# ProPrj_LoRA_Transmitter_Atmega328u_2025-.net
KiCad netlist of a schematic drawn in EasyEDA Pro
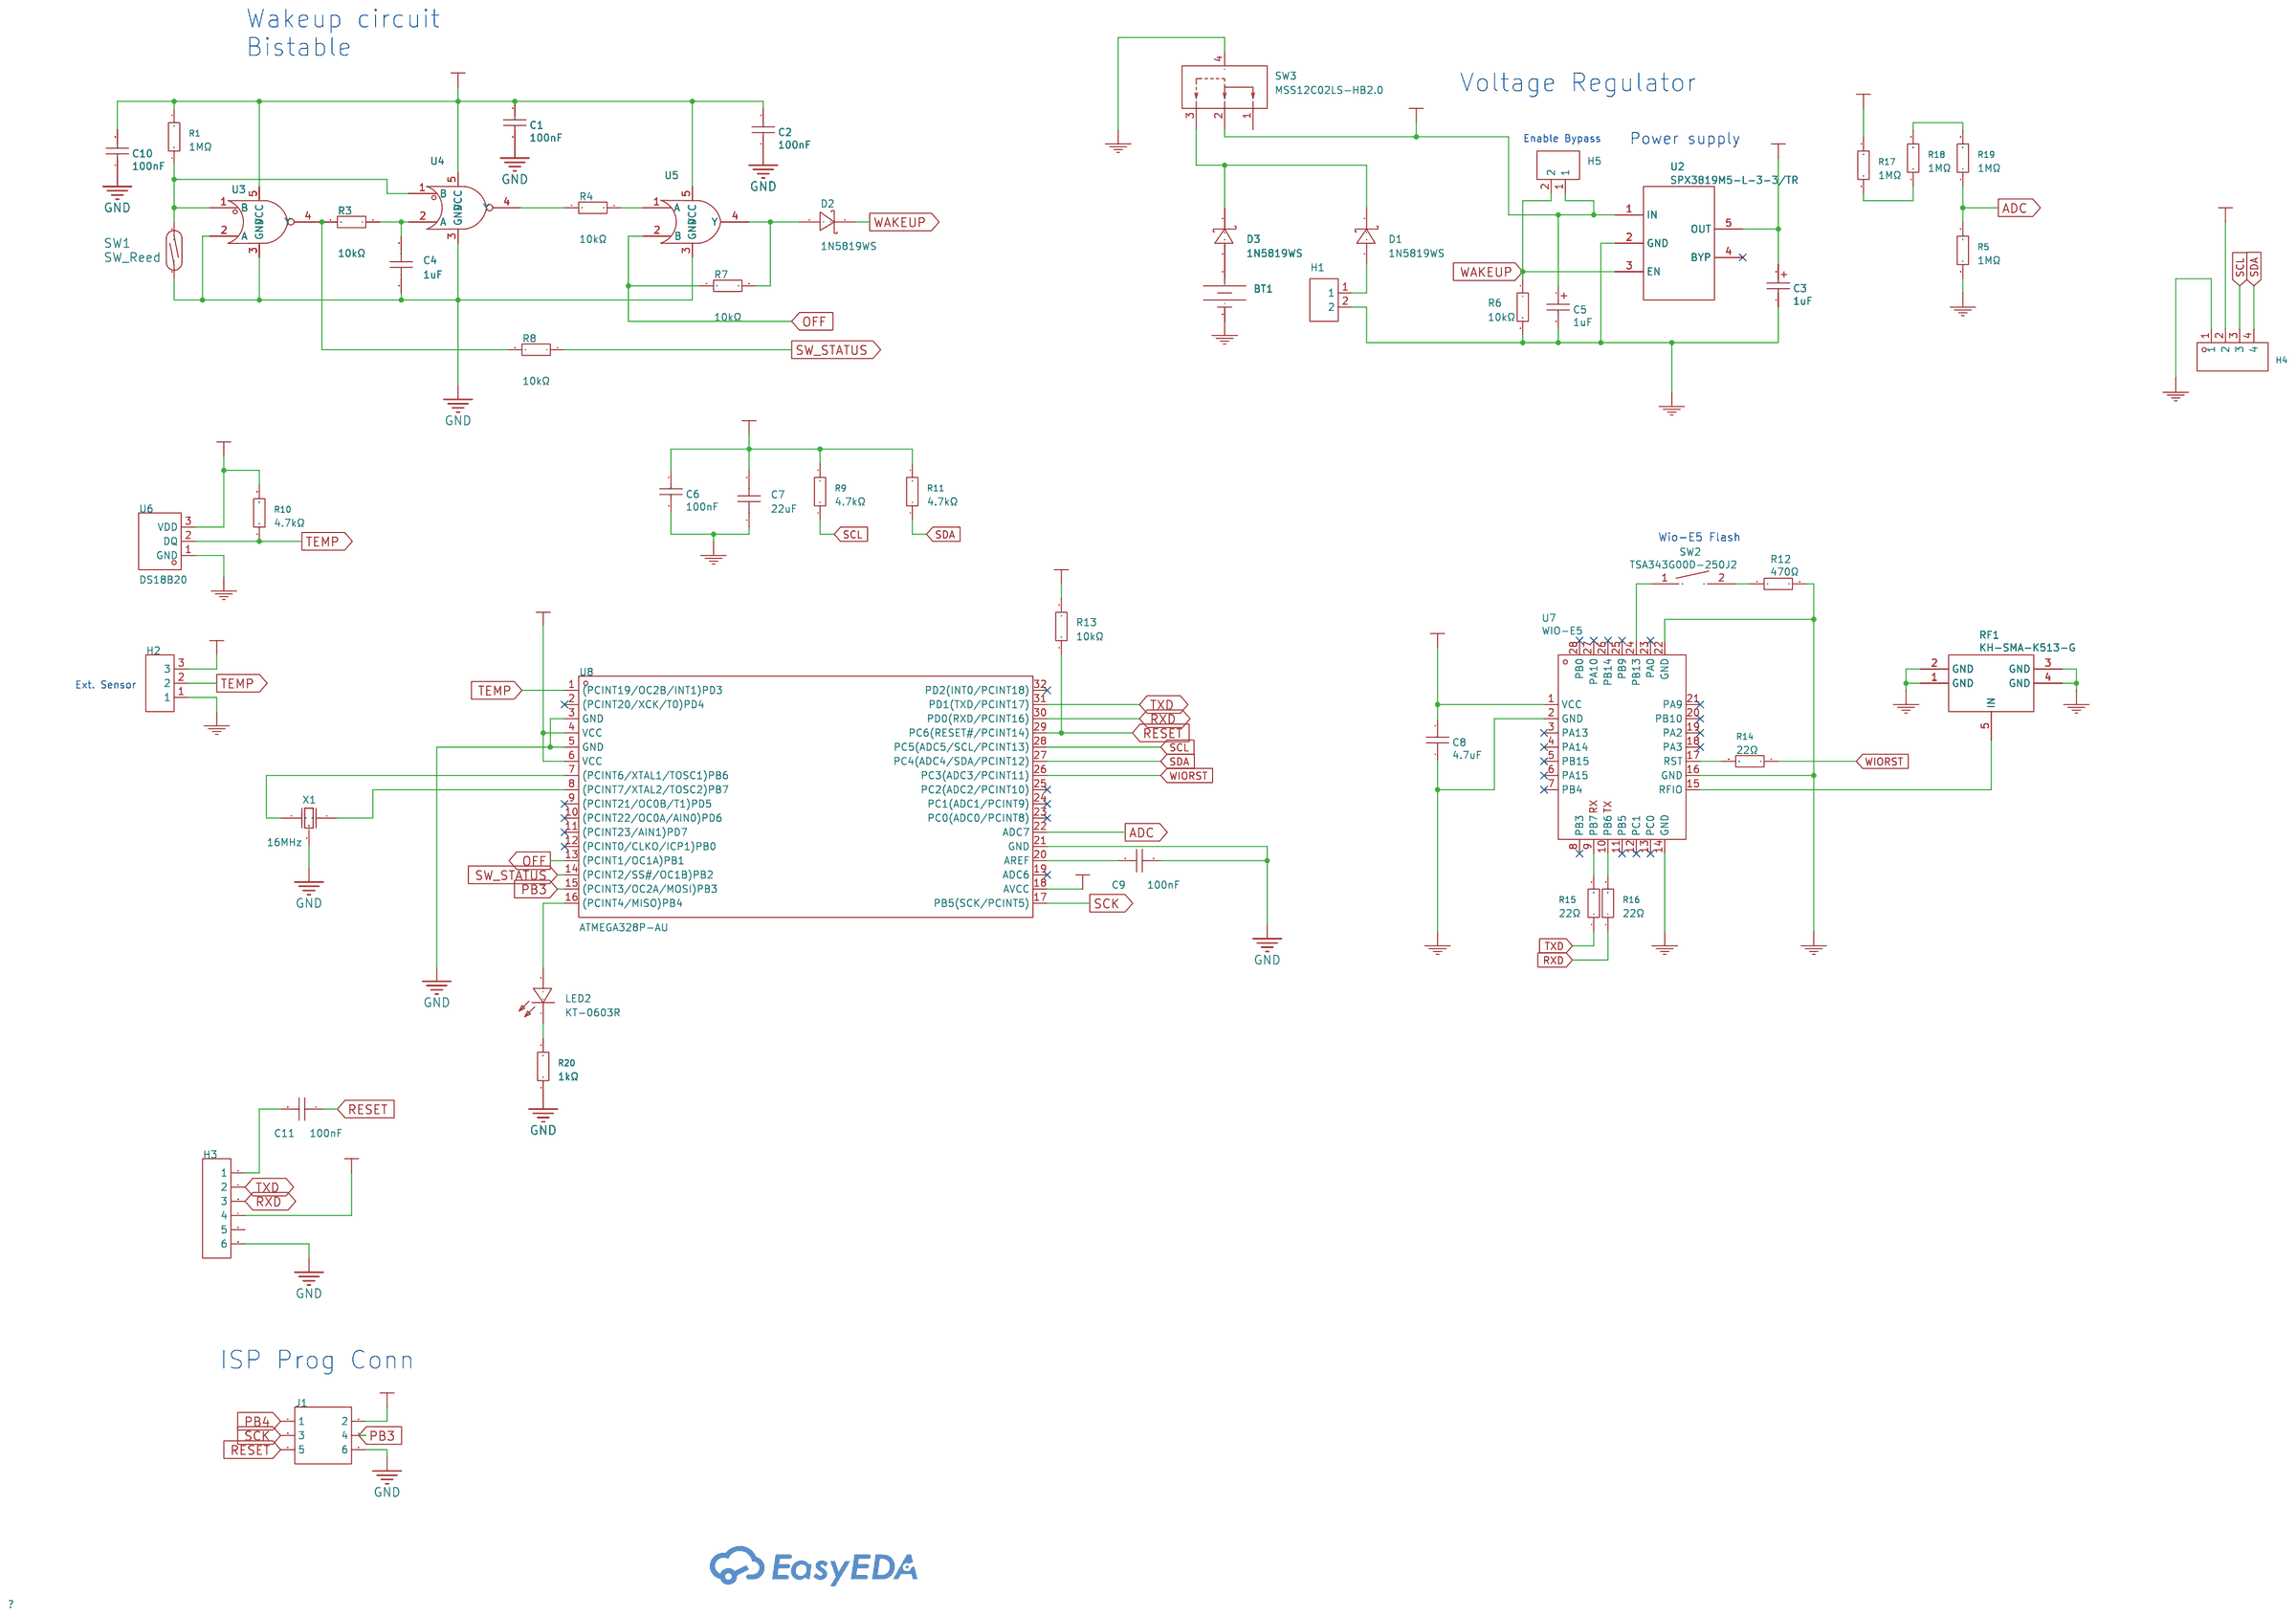
[diagram p0: schematic sheet]

(export (version "E")
  (design (tool "Eeschema 10.0.6"))
  (components
    (comp (ref "BT1")
      (value "BH-18650-4")
      (footprint "easyedapro:BAT-SMD_BH-18650-4")
      (fields (field (name "Manufacturer") "HanElectricity(瀚源)"))
      (libsource (lib "easyedapro") (part "BH-18650-4"))
    )
    (comp (ref "C1") (value "100nF") (libsource (lib "easyedapro") (part "100nF")))
    (comp (ref "C2") (value "100nF") (libsource (lib "easyedapro") (part "100nF")))
    (comp (ref "C3")
      (value "1uF")
      (footprint "easyedapro:footprint_777a")
      (fields (field (name "Manufacturer Part") "TAJA105K035RNJ") (field (name "Manufacturer") "Kyocera AVX"))
      (libsource (lib "easyedapro") (part "1uF"))
    )
    (comp (ref "C4")
      (value "1uF")
      (footprint "easyedapro:C0402")
      (description "Capacitance:1uF Tolerance:±10% Tolerance:±10% Voltage Rating:25V Temperature Coefficient:X5R")
      (fields
        (field (name "Manufacturer Part") "CL05A105KA5NQNC")
        (field (name "Manufacturer") "SAMSUNG(三星)")
      )
      (libsource (lib "easyedapro") (part "CL05A105KA5NQNC"))
    )
    (comp (ref "C5")
      (value "1uF")
      (footprint "easyedapro:footprint_777a")
      (fields (field (name "Manufacturer Part") "TAJA105K035RNJ") (field (name "Manufacturer") "Kyocera AVX"))
      (libsource (lib "easyedapro") (part "1uF"))
    )
    (comp (ref "C6") (value "100nF") (libsource (lib "easyedapro") (part "100nF")))
    (comp (ref "C7")
      (value "22uF")
      (footprint "easyedapro:C0603")
      (fields
        (field (name "Manufacturer Part") "CL10A226MQ8NRNC")
        (field (name "Manufacturer") "SAMSUNG(三星)")
      )
      (libsource (lib "easyedapro") (part "CL10A226MQ8NRNC"))
    )
    (comp (ref "C8")
      (value "4.7uF")
      (footprint "easyedapro:footprint_3af0")
      (fields
        (field (name "Manufacturer Part") "CL10A475KO8NNNC")
        (field (name "Manufacturer") "SAMSUNG(三星)")
      )
      (libsource (lib "easyedapro") (part "4.7uF"))
    )
    (comp (ref "C9") (value "100nF") (libsource (lib "easyedapro") (part "100nF")))
    (comp (ref "C10") (value "100nF") (libsource (lib "easyedapro") (part "100nF")))
    (comp (ref "C11") (value "100nF") (libsource (lib "easyedapro") (part "100nF")))
    (comp (ref "D1")
      (value "1N5819WS")
      (footprint "easyedapro:SOD-323_L1.8-W1.3-LS2.5-RD")
      (description "Forward Voltage (Vf@If):600mV@1A Reverse Voltage (Vr):40V Rectified Current:1A")
      (fields (field (name "Manufacturer") "Hottech(合科泰)"))
      (libsource (lib "easyedapro") (part "1N5819WS"))
    )
    (comp (ref "D2")
      (value "1N5819WS")
      (footprint "easyedapro:SOD-323_L1.8-W1.3-LS2.5-RD")
      (description "Forward Voltage (Vf@If):600mV@1A Reverse Voltage (Vr):40V Rectified Current:1A")
      (fields (field (name "Manufacturer") "Hottech(合科泰)"))
      (libsource (lib "easyedapro") (part "1N5819WS"))
    )
    (comp (ref "D3")
      (value "1N5819WS")
      (footprint "easyedapro:SOD-323_L1.8-W1.3-LS2.5-RD")
      (description "Forward Voltage (Vf@If):600mV@1A Reverse Voltage (Vr):40V Rectified Current:1A")
      (fields (field (name "Manufacturer") "Hottech(合科泰)"))
      (libsource (lib "easyedapro") (part "1N5819WS"))
    )
    (comp (ref "H1")
      (value "PZ254V-11-02P")
      (footprint "easyedapro:HDR-TH_2P-P2.54-V-M")
      (fields (field (name "Manufacturer") "XFCN(兴飞)"))
      (libsource (lib "easyedapro") (part "PZ254V-11-02P"))
    )
    (comp (ref "H2")
      (value "PZ254V-11-03P")
      (footprint "easyedapro:HDR-TH_3P-P2.54-V-M")
      (fields (field (name "Manufacturer") "XFCN(兴飞)"))
      (libsource (lib "easyedapro") (part "PZ254V-11-03P_C2937625"))
    )
    (comp (ref "H3")
      (value "2.54-1x6P直针")
      (footprint "easyedapro:HDR-TH_6P-P2.54-V-M-1")
      (fields (field (name "Manufacturer") "BOOMELE(博穆精密)"))
      (libsource (lib "easyedapro") (part "Header-Male-2.54_1x6"))
    )
    (comp (ref "H4")
      (value "PZ254V-11-04P")
      (footprint "easyedapro:HDR-TH_4P-P2.54-V-M")
      (fields (field (name "Manufacturer") "XFCN(兴飞)"))
      (libsource (lib "easyedapro") (part "PZ254V-11-04P_C2691448"))
    )
    (comp (ref "H5")
      (value "PZ254V-11-02P")
      (footprint "easyedapro:HDR-TH_2P-P2.54-V-M")
      (fields (field (name "Manufacturer") "XFCN(兴飞)"))
      (libsource (lib "easyedapro") (part "PZ254V-11-02P"))
    )
    (comp (ref "J1")
      (value "2.54-2*3P针")
      (footprint "easyedapro:HDR-TH_6P-P2.54-V-M-R2-C3-S2.54-1")
      (fields (field (name "Manufacturer") "BOOMELE(博穆精密)"))
      (libsource (lib "easyedapro") (part "Header-Male-2.54_2x3"))
    )
    (comp (ref "LED2")
      (value "KT-0603R")
      (footprint "easyedapro:LED0603-RD")
      (fields (field (name "Manufacturer") "KENTO"))
      (libsource (lib "easyedapro") (part "KT-0603R"))
    )
    (comp (ref "R1")
      (value "1MΩ")
      (footprint "easyedapro:R0402")
      (fields
        (field (name "Manufacturer Part") "0402WGF1004TCE")
        (field (name "Manufacturer") "UNI-ROYAL(厚声)")
      )
      (libsource (lib "easyedapro") (part "0402WGF1004TCE"))
    )
    (comp (ref "R3")
      (value "10kΩ")
      (footprint "easyedapro:R0402")
      (fields
        (field (name "Manufacturer Part") "0402WGF1002TCE")
        (field (name "Manufacturer") "UNI-ROYAL(厚声)")
      )
      (libsource (lib "easyedapro") (part "0402WGF1002TCE"))
    )
    (comp (ref "R4")
      (value "10kΩ")
      (footprint "easyedapro:R0402")
      (fields
        (field (name "Manufacturer Part") "0402WGF1002TCE")
        (field (name "Manufacturer") "UNI-ROYAL(厚声)")
      )
      (libsource (lib "easyedapro") (part "0402WGF1002TCE"))
    )
    (comp (ref "R5")
      (value "1MΩ")
      (footprint "easyedapro:R0402")
      (fields
        (field (name "Manufacturer Part") "0402WGF1004TCE")
        (field (name "Manufacturer") "UNI-ROYAL(厚声)")
      )
      (libsource (lib "easyedapro") (part "0402WGF1004TCE"))
    )
    (comp (ref "R6")
      (value "10kΩ")
      (footprint "easyedapro:R0402")
      (fields
        (field (name "Manufacturer Part") "0402WGF1002TCE")
        (field (name "Manufacturer") "UNI-ROYAL(厚声)")
      )
      (libsource (lib "easyedapro") (part "0402WGF1002TCE"))
    )
    (comp (ref "R7")
      (value "10kΩ")
      (footprint "easyedapro:R0402")
      (fields
        (field (name "Manufacturer Part") "0402WGF1002TCE")
        (field (name "Manufacturer") "UNI-ROYAL(厚声)")
      )
      (libsource (lib "easyedapro") (part "0402WGF1002TCE"))
    )
    (comp (ref "R8")
      (value "10kΩ")
      (footprint "easyedapro:R0402")
      (fields
        (field (name "Manufacturer Part") "0402WGF1002TCE")
        (field (name "Manufacturer") "UNI-ROYAL(厚声)")
      )
      (libsource (lib "easyedapro") (part "0402WGF1002TCE"))
    )
    (comp (ref "R9")
      (value "4.7kΩ")
      (footprint "easyedapro:R0402")
      (fields
        (field (name "Manufacturer Part") "0402WGF4701TCE")
        (field (name "Manufacturer") "UNI-ROYAL(厚声)")
      )
      (libsource (lib "easyedapro") (part "0402WGF4701TCE"))
    )
    (comp (ref "R10")
      (value "4.7kΩ")
      (footprint "easyedapro:R0402")
      (fields
        (field (name "Manufacturer Part") "0402WGF4701TCE")
        (field (name "Manufacturer") "UNI-ROYAL(厚声)")
      )
      (libsource (lib "easyedapro") (part "0402WGF4701TCE"))
    )
    (comp (ref "R11")
      (value "4.7kΩ")
      (footprint "easyedapro:R0402")
      (fields
        (field (name "Manufacturer Part") "0402WGF4701TCE")
        (field (name "Manufacturer") "UNI-ROYAL(厚声)")
      )
      (libsource (lib "easyedapro") (part "0402WGF4701TCE"))
    )
    (comp (ref "R12")
      (value "470Ω")
      (footprint "easyedapro:footprint_9035")
      (fields (field (name "Manufacturer Part") "0603WAF4700T5E") (field (name "Manufacturer") "UniOhm"))
      (libsource (lib "easyedapro") (part "470Ω"))
    )
    (comp (ref "R13")
      (value "10kΩ")
      (footprint "easyedapro:R0402")
      (fields
        (field (name "Manufacturer Part") "0402WGF1002TCE")
        (field (name "Manufacturer") "UNI-ROYAL(厚声)")
      )
      (libsource (lib "easyedapro") (part "0402WGF1002TCE"))
    )
    (comp (ref "R14")
      (value "22Ω")
      (footprint "easyedapro:R0402")
      (fields
        (field (name "Manufacturer Part") "0402WGF220JTCE")
        (field (name "Manufacturer") "UNI-ROYAL(厚声)")
      )
      (libsource (lib "easyedapro") (part "0402WGF220JTCE"))
    )
    (comp (ref "R15")
      (value "22Ω")
      (footprint "easyedapro:R0402")
      (fields
        (field (name "Manufacturer Part") "0402WGF220JTCE")
        (field (name "Manufacturer") "UNI-ROYAL(厚声)")
      )
      (libsource (lib "easyedapro") (part "0402WGF220JTCE"))
    )
    (comp (ref "R16")
      (value "22Ω")
      (footprint "easyedapro:R0402")
      (fields
        (field (name "Manufacturer Part") "0402WGF220JTCE")
        (field (name "Manufacturer") "UNI-ROYAL(厚声)")
      )
      (libsource (lib "easyedapro") (part "0402WGF220JTCE"))
    )
    (comp (ref "R17")
      (value "1MΩ")
      (footprint "easyedapro:R0402")
      (fields
        (field (name "Manufacturer Part") "0402WGF1004TCE")
        (field (name "Manufacturer") "UNI-ROYAL(厚声)")
      )
      (libsource (lib "easyedapro") (part "0402WGF1004TCE"))
    )
    (comp (ref "R18")
      (value "1MΩ")
      (footprint "easyedapro:R0402")
      (fields
        (field (name "Manufacturer Part") "0402WGF1004TCE")
        (field (name "Manufacturer") "UNI-ROYAL(厚声)")
      )
      (libsource (lib "easyedapro") (part "0402WGF1004TCE"))
    )
    (comp (ref "R19")
      (value "1MΩ")
      (footprint "easyedapro:R0402")
      (fields
        (field (name "Manufacturer Part") "0402WGF1004TCE")
        (field (name "Manufacturer") "UNI-ROYAL(厚声)")
      )
      (libsource (lib "easyedapro") (part "0402WGF1004TCE"))
    )
    (comp (ref "R20")
      (value "1kΩ")
      (footprint "easyedapro:R0402")
      (fields
        (field (name "Manufacturer Part") "0402WGF1001TCE")
        (field (name "Manufacturer") "UNI-ROYAL(厚声)")
      )
      (libsource (lib "easyedapro") (part "0402WGF1001TCE"))
    )
    (comp (ref "RF1")
      (value "KH-SMA-K513-G")
      (footprint "easyedapro:footprint_7c52")
      (fields (field (name "Manufacturer") "kinghelm(金航标)"))
      (libsource (lib "easyedapro") (part "KH-SMA-K513-G"))
    )
    (comp (ref "SW1") (value "SW_Reed") (libsource (lib "easyedapro") (part "Switch_SW_Reed")))
    (comp (ref "SW2")
      (value "TSA343G00D-250J2")
      (footprint "easyedapro:footprint_b169")
      (fields (field (name "Manufacturer") "BRIGHT(博瑞泰)"))
      (libsource (lib "easyedapro") (part "TSA343G00D-250J2"))
    )
    (comp (ref "SW3")
      (value "MSS12C02LS-HB2.0")
      (footprint "easyedapro:SW-SMD_MSS12C02LS-HB2.0-1")
      (fields (field (name "Manufacturer") "SHOU HAN(首韩)"))
      (libsource (lib "easyedapro") (part "MSS12C02LS-HB2.0"))
    )
    (comp (ref "U2")
      (value "SPX3819M5-L-3-3/TR")
      (footprint "easyedapro:footprint_c1b7")
      (fields (field (name "Manufacturer") "MaxLinear"))
      (libsource (lib "easyedapro") (part "SPX3819M5-L-3-3/TR"))
    )
    (comp (ref "U3")
      (value "74AHC1G86GW,125")
      (footprint "easyedapro:SOT-353-5_L2.0-W1.3-P0.65-LS2.1-BR")
      (fields (field (name "Manufacturer") "Nexperia(安世)"))
      (libsource (lib "easyedapro") (part "74AHC1G86GW,125"))
    )
    (comp (ref "U4")
      (value "74AHC1G86GW,125")
      (footprint "easyedapro:SOT-353-5_L2.0-W1.3-P0.65-LS2.1-BR")
      (fields (field (name "Manufacturer") "Nexperia(安世)"))
      (libsource (lib "easyedapro") (part "74AHC1G86GW,125"))
    )
    (comp (ref "U5")
      (value "SN74AHC1G32DBVR")
      (footprint "easyedapro:SOT-23-5_L3.0-W1.7-P0.95-LS2.8-BR")
      (fields (field (name "Manufacturer") "TI(德州仪器)"))
      (libsource (lib "easyedapro") (part "SN74AHC1G32DBVR"))
    )
    (comp (ref "U6")
      (value "DS18B20")
      (footprint "easyedapro:TO-92-3_L4.5-W3.5-P1.27-L")
      (fields (field (name "Manufacturer") "HXY MOSFET(华轩阳电子)"))
      (libsource (lib "easyedapro") (part "DS18B20_C5451632"))
    )
    (comp (ref "U7")
      (value "WIO-E5")
      (footprint "easyedapro:footprint_0a5f")
      (fields (field (name "Manufacturer Part") "LoRa-E5"))
      (libsource (lib "easyedapro") (part "WIO-E5"))
    )
    (comp (ref "U8")
      (value "ATMEGA328P-AU")
      (footprint "easyedapro:TQFP-32_L7.0-W7.0-P0.80-LS9.0-BL")
      (fields (field (name "Manufacturer") "MICROCHIP(美国微芯)"))
      (libsource (lib "easyedapro") (part "ATMEGA328P-AU"))
    )
    (comp (ref "X1")
      (value "16MHz")
      (footprint "easyedapro:OSC-SMD_3P-L3.2-W1.3-P1.20-L")
      (fields
        (field (name "Manufacturer Part") "CSTNE16M0V53L000R0")
        (field (name "Manufacturer") "muRata(村田)")
      )
      (libsource (lib "easyedapro") (part "CSTNE16M0V53L000R0"))
    )
  )
  (nets
    (net (code "1") (name "ADC") (class "Default")
      (node (ref "R19") (pin "1") (pinfunction "1_1") (pintype "input"))
      (node (ref "R5") (pin "2") (pinfunction "2_2") (pintype "input"))
      (node (ref "U8") (pin "22") (pinfunction "ADC7_22") (pintype "unspecified"))
    )
    (net (code "2") (name "GND") (class "Default")
      (node (ref "BT1") (pin "2") (pinfunction "-_2") (pintype "unspecified"))
      (node (ref "C1") (pin "1") (pinfunction "1_1") (pintype "input"))
      (node (ref "C10") (pin "1") (pinfunction "1_1") (pintype "input"))
      (node (ref "C2") (pin "1") (pinfunction "1_1") (pintype "input"))
      (node (ref "C3") (pin "2") (pinfunction "2_2") (pintype "input"))
      (node (ref "C4") (pin "1") (pinfunction "1_1") (pintype "unspecified"))
      (node (ref "C5") (pin "2") (pinfunction "2_2") (pintype "input"))
      (node (ref "C6") (pin "1") (pinfunction "1_1") (pintype "input"))
      (node (ref "C7") (pin "1") (pinfunction "1_1") (pintype "unspecified"))
      (node (ref "C8") (pin "1") (pinfunction "1_1") (pintype "input"))
      (node (ref "C9") (pin "1") (pinfunction "1_1") (pintype "input"))
      (node (ref "H1") (pin "2") (pinfunction "2_2") (pintype "unspecified"))
      (node (ref "H2") (pin "1") (pinfunction "1_1") (pintype "unspecified"))
      (node (ref "H3") (pin "6") (pinfunction "6_6") (pintype "input"))
      (node (ref "H4") (pin "1") (pinfunction "1_1") (pintype "input"))
      (node (ref "J1") (pin "6") (pinfunction "6_6") (pintype "input"))
      (node (ref "R12") (pin "2") (pinfunction "2_2") (pintype "input"))
      (node (ref "R20") (pin "1") (pinfunction "1_1") (pintype "input"))
      (node (ref "R5") (pin "1") (pinfunction "1_1") (pintype "input"))
      (node (ref "R6") (pin "2") (pinfunction "2_2") (pintype "input"))
      (node (ref "RF1") (pin "1") (pinfunction "GND_1") (pintype "unspecified"))
      (node (ref "RF1") (pin "2") (pinfunction "GND_2") (pintype "unspecified"))
      (node (ref "RF1") (pin "3") (pinfunction "GND_3") (pintype "unspecified"))
      (node (ref "RF1") (pin "4") (pinfunction "GND_4") (pintype "unspecified"))
      (node (ref "SW1") (pin "1") (pinfunction "1_1") (pintype "input"))
      (node (ref "SW3") (pin "4") (pinfunction "4_4") (pintype "unspecified"))
      (node (ref "U2") (pin "2") (pinfunction "GND_2") (pintype "unspecified"))
      (node (ref "U3") (pin "2") (pinfunction "A_2") (pintype "unspecified"))
      (node (ref "U3") (pin "3") (pinfunction "GND_3") (pintype "unspecified"))
      (node (ref "U4") (pin "3") (pinfunction "GND_3") (pintype "unspecified"))
      (node (ref "U5") (pin "3") (pinfunction "GND_3") (pintype "unspecified"))
      (node (ref "U6") (pin "1") (pinfunction "GND_1") (pintype "unspecified"))
      (node (ref "U7") (pin "14") (pinfunction "GND_14") (pintype "unspecified"))
      (node (ref "U7") (pin "16") (pinfunction "GND_16") (pintype "unspecified"))
      (node (ref "U7") (pin "2") (pinfunction "GND_2") (pintype "unspecified"))
      (node (ref "U7") (pin "22") (pinfunction "GND_22") (pintype "unspecified"))
      (node (ref "U8") (pin "21") (pinfunction "GND_21") (pintype "unspecified"))
      (node (ref "U8") (pin "3") (pinfunction "GND_3") (pintype "unspecified"))
      (node (ref "U8") (pin "5") (pinfunction "GND_5") (pintype "unspecified"))
      (node (ref "X1") (pin "2") (pinfunction "GND_2") (pintype "input"))
    )
    (net (code "3") (name "Net-(BT1-+)") (class "Default")
      (node (ref "BT1") (pin "1") (pinfunction "+_1") (pintype "unspecified"))
      (node (ref "D3") (pin "2") (pinfunction "A_2") (pintype "unspecified"))
    )
    (net (code "4") (name "Net-(C11-Pad2)") (class "Default")
      (node (ref "C11") (pin "2") (pinfunction "2_2") (pintype "input"))
      (node (ref "H3") (pin "1") (pinfunction "1_1") (pintype "input"))
    )
    (net (code "5") (name "Net-(D1-A)") (class "Default")
      (node (ref "D1") (pin "2") (pinfunction "A_2") (pintype "unspecified"))
      (node (ref "H1") (pin "1") (pinfunction "1_1") (pintype "unspecified"))
    )
    (net (code "6") (name "Net-(D1-K)") (class "Default")
      (node (ref "D1") (pin "1") (pinfunction "K_1") (pintype "unspecified"))
      (node (ref "D3") (pin "1") (pinfunction "K_1") (pintype "unspecified"))
      (node (ref "SW3") (pin "3") (pinfunction "3_3") (pintype "unspecified"))
    )
    (net (code "7") (name "Net-(D2-A)") (class "Default")
      (node (ref "D2") (pin "2") (pinfunction "A_2") (pintype "unspecified"))
      (node (ref "R7") (pin "1") (pinfunction "1_1") (pintype "input"))
      (node (ref "U5") (pin "4") (pinfunction "Y_4") (pintype "unspecified"))
    )
    (net (code "8") (name "Net-(LED2-A)") (class "Default")
      (node (ref "LED2") (pin "2") (pinfunction "A_2") (pintype "unspecified"))
      (node (ref "U8") (pin "16") (pinfunction "(PCINT4/MISO)PB4_16") (pintype "unspecified"))
    )
    (net (code "9") (name "Net-(LED2-K)") (class "Default")
      (node (ref "LED2") (pin "1") (pinfunction "K_1") (pintype "unspecified"))
      (node (ref "R20") (pin "2") (pinfunction "2_2") (pintype "input"))
    )
    (net (code "10") (name "Net-(R12-Pad1)") (class "Default")
      (node (ref "R12") (pin "1") (pinfunction "1_1") (pintype "input"))
      (node (ref "SW2") (pin "2") (pinfunction "2_2") (pintype "input"))
    )
    (net (code "11") (name "Net-(R17-Pad1)") (class "Default")
      (node (ref "R17") (pin "1") (pinfunction "1_1") (pintype "input"))
      (node (ref "R18") (pin "1") (pinfunction "1_1") (pintype "input"))
    )
    (net (code "12") (name "Net-(R18-Pad2)") (class "Default")
      (node (ref "R18") (pin "2") (pinfunction "2_2") (pintype "input"))
      (node (ref "R19") (pin "2") (pinfunction "2_2") (pintype "input"))
    )
    (net (code "13") (name "Net-(RF1-IN)") (class "Default")
      (node (ref "RF1") (pin "5") (pinfunction "IN_5") (pintype "unspecified"))
      (node (ref "U7") (pin "15") (pinfunction "RFIO_15") (pintype "unspecified"))
    )
    (net (code "14") (name "Net-(U3-B)") (class "Default")
      (node (ref "R1") (pin "1") (pinfunction "1_1") (pintype "input"))
      (node (ref "SW1") (pin "2") (pinfunction "2_2") (pintype "input"))
      (node (ref "U3") (pin "1") (pinfunction "B_1") (pintype "unspecified"))
      (node (ref "U4") (pin "1") (pinfunction "B_1") (pintype "unspecified"))
    )
    (net (code "15") (name "Net-(U3-Y)") (class "Default")
      (node (ref "R3") (pin "2") (pinfunction "2_2") (pintype "input"))
      (node (ref "R8") (pin "2") (pinfunction "2_2") (pintype "input"))
      (node (ref "U3") (pin "4") (pinfunction "Y_4") (pintype "unspecified"))
    )
    (net (code "16") (name "Net-(U4-A)") (class "Default")
      (node (ref "C4") (pin "2") (pinfunction "2_2") (pintype "unspecified"))
      (node (ref "R3") (pin "1") (pinfunction "1_1") (pintype "input"))
      (node (ref "U4") (pin "2") (pinfunction "A_2") (pintype "unspecified"))
    )
    (net (code "17") (name "Net-(U4-Y)") (class "Default")
      (node (ref "R4") (pin "2") (pinfunction "2_2") (pintype "input"))
      (node (ref "U4") (pin "4") (pinfunction "Y_4") (pintype "unspecified"))
    )
    (net (code "18") (name "Net-(U5-A)") (class "Default")
      (node (ref "R4") (pin "1") (pinfunction "1_1") (pintype "input"))
      (node (ref "U5") (pin "1") (pinfunction "A_1") (pintype "unspecified"))
    )
    (net (code "19") (name "Net-(U7-PB6)") (class "Default")
      (node (ref "R16") (pin "2") (pinfunction "2_2") (pintype "input"))
      (node (ref "U7") (pin "10") (pinfunction "PB6_10") (pintype "unspecified"))
    )
    (net (code "20") (name "Net-(U7-PB7)") (class "Default")
      (node (ref "R15") (pin "2") (pinfunction "2_2") (pintype "input"))
      (node (ref "U7") (pin "9") (pinfunction "PB7_9") (pintype "unspecified"))
    )
    (net (code "21") (name "Net-(U7-PB13)") (class "Default")
      (node (ref "SW2") (pin "1") (pinfunction "1_1") (pintype "input"))
      (node (ref "U7") (pin "24") (pinfunction "PB13_24") (pintype "unspecified"))
    )
    (net (code "22") (name "Net-(U7-RST)") (class "Default")
      (node (ref "R14") (pin "2") (pinfunction "2_2") (pintype "input"))
      (node (ref "U7") (pin "17") (pinfunction "RST_17") (pintype "unspecified"))
    )
    (net (code "23") (name "Net-(U8-(PCINT6{slash}XTAL1{slash}TOSC1)PB6)") (class "Default")
      (node (ref "U8") (pin "7") (pinfunction "(PCINT6/XTAL1/TOSC1)PB6_7") (pintype "unspecified"))
      (node (ref "X1") (pin "3") (pinfunction "OSC2_3") (pintype "input"))
    )
    (net (code "24") (name "Net-(U8-(PCINT7{slash}XTAL2{slash}TOSC2)PB7)") (class "Default")
      (node (ref "U8") (pin "8") (pinfunction "(PCINT7/XTAL2/TOSC2)PB7_8") (pintype "unspecified"))
      (node (ref "X1") (pin "1") (pinfunction "OSC1_1") (pintype "input"))
    )
    (net (code "25") (name "Net-(U8-AREF)") (class "Default")
      (node (ref "C9") (pin "2") (pinfunction "2_2") (pintype "input"))
      (node (ref "U8") (pin "20") (pinfunction "AREF_20") (pintype "unspecified"))
    )
    (net (code "26") (name "OFF") (class "Default")
      (node (ref "R7") (pin "2") (pinfunction "2_2") (pintype "input"))
      (node (ref "U5") (pin "2") (pinfunction "B_2") (pintype "unspecified"))
      (node (ref "U8") (pin "13") (pinfunction "(PCINT1/OC1A)PB1_13") (pintype "unspecified"))
    )
    (net (code "27") (name "PB3") (class "Default")
      (node (ref "J1") (pin "4") (pinfunction "4_4") (pintype "input"))
      (node (ref "U8") (pin "15") (pinfunction "(PCINT3/OC2A/MOSI)PB3_15") (pintype "unspecified"))
    )
    (net (code "28") (name "PB4") (class "Default")
      (node (ref "J1") (pin "1") (pinfunction "1_1") (pintype "input"))
    )
    (net (code "29") (name "RESET") (class "Default")
      (node (ref "C11") (pin "1") (pinfunction "1_1") (pintype "input"))
      (node (ref "J1") (pin "5") (pinfunction "5_5") (pintype "input"))
      (node (ref "R13") (pin "1") (pinfunction "1_1") (pintype "input"))
      (node (ref "U8") (pin "29") (pinfunction "PC6(RESET#/PCINT14)_29") (pintype "unspecified"))
    )
    (net (code "30") (name "RXD") (class "Default")
      (node (ref "H3") (pin "3") (pinfunction "3_3") (pintype "input"))
      (node (ref "R16") (pin "1") (pinfunction "1_1") (pintype "input"))
      (node (ref "U8") (pin "30") (pinfunction "PD0(RXD/PCINT16)_30") (pintype "unspecified"))
    )
    (net (code "31") (name "SCK") (class "Default")
      (node (ref "J1") (pin "3") (pinfunction "3_3") (pintype "input"))
      (node (ref "U8") (pin "17") (pinfunction "PB5(SCK/PCINT5)_17") (pintype "unspecified"))
    )
    (net (code "32") (name "SCL") (class "Default")
      (node (ref "H4") (pin "3") (pinfunction "3_3") (pintype "input"))
      (node (ref "R9") (pin "1") (pinfunction "1_1") (pintype "input"))
      (node (ref "U8") (pin "28") (pinfunction "PC5(ADC5/SCL/PCINT13)_28") (pintype "unspecified"))
    )
    (net (code "33") (name "SDA") (class "Default")
      (node (ref "H4") (pin "4") (pinfunction "4_4") (pintype "input"))
      (node (ref "R11") (pin "1") (pinfunction "1_1") (pintype "input"))
      (node (ref "U8") (pin "27") (pinfunction "PC4(ADC4/SDA/PCINT12)_27") (pintype "unspecified"))
    )
    (net (code "34") (name "SW_STATUS") (class "Default")
      (node (ref "R8") (pin "1") (pinfunction "1_1") (pintype "input"))
      (node (ref "U8") (pin "14") (pinfunction "(PCINT2/SS#/OC1B)PB2_14") (pintype "unspecified"))
    )
    (net (code "35") (name "TEMP") (class "Default")
      (node (ref "H2") (pin "2") (pinfunction "2_2") (pintype "unspecified"))
      (node (ref "R10") (pin "1") (pinfunction "1_1") (pintype "input"))
      (node (ref "U6") (pin "2") (pinfunction "DQ_2") (pintype "unspecified"))
      (node (ref "U8") (pin "1") (pinfunction "(PCINT19/OC2B/INT1)PD3_1") (pintype "unspecified"))
    )
    (net (code "36") (name "TXD") (class "Default")
      (node (ref "H3") (pin "2") (pinfunction "2_2") (pintype "input"))
      (node (ref "R15") (pin "1") (pinfunction "1_1") (pintype "input"))
      (node (ref "U8") (pin "31") (pinfunction "PD1(TXD/PCINT17)_31") (pintype "unspecified"))
    )
    (net (code "37") (name "VBATT") (class "Default")
      (node (ref "C1") (pin "2") (pinfunction "2_2") (pintype "input"))
      (node (ref "C10") (pin "2") (pinfunction "2_2") (pintype "input"))
      (node (ref "C2") (pin "2") (pinfunction "2_2") (pintype "input"))
      (node (ref "C5") (pin "1") (pinfunction "1_1") (pintype "input"))
      (node (ref "H5") (pin "1") (pinfunction "1_1") (pintype "unspecified"))
      (node (ref "R1") (pin "2") (pinfunction "2_2") (pintype "input"))
      (node (ref "R17") (pin "2") (pinfunction "2_2") (pintype "input"))
      (node (ref "SW3") (pin "2") (pinfunction "2_2") (pintype "unspecified"))
      (node (ref "U2") (pin "1") (pinfunction "IN_1") (pintype "unspecified"))
      (node (ref "U3") (pin "5") (pinfunction "VCC_5") (pintype "unspecified"))
      (node (ref "U4") (pin "5") (pinfunction "VCC_5") (pintype "unspecified"))
      (node (ref "U5") (pin "5") (pinfunction "VCC_5") (pintype "unspecified"))
    )
    (net (code "38") (name "VCC") (class "Default")
      (node (ref "C3") (pin "1") (pinfunction "1_1") (pintype "input"))
      (node (ref "C6") (pin "2") (pinfunction "2_2") (pintype "input"))
      (node (ref "C7") (pin "2") (pinfunction "2_2") (pintype "unspecified"))
      (node (ref "C8") (pin "2") (pinfunction "2_2") (pintype "input"))
      (node (ref "H2") (pin "3") (pinfunction "3_3") (pintype "unspecified"))
      (node (ref "H3") (pin "4") (pinfunction "4_4") (pintype "input"))
      (node (ref "H4") (pin "2") (pinfunction "2_2") (pintype "input"))
      (node (ref "J1") (pin "2") (pinfunction "2_2") (pintype "input"))
      (node (ref "R10") (pin "2") (pinfunction "2_2") (pintype "input"))
      (node (ref "R11") (pin "2") (pinfunction "2_2") (pintype "input"))
      (node (ref "R13") (pin "2") (pinfunction "2_2") (pintype "input"))
      (node (ref "R9") (pin "2") (pinfunction "2_2") (pintype "input"))
      (node (ref "U2") (pin "5") (pinfunction "OUT_5") (pintype "unspecified"))
      (node (ref "U6") (pin "3") (pinfunction "VDD_3") (pintype "unspecified"))
      (node (ref "U7") (pin "1") (pinfunction "VCC_1") (pintype "unspecified"))
      (node (ref "U8") (pin "18") (pinfunction "AVCC_18") (pintype "unspecified"))
      (node (ref "U8") (pin "4") (pinfunction "VCC_4") (pintype "unspecified"))
      (node (ref "U8") (pin "6") (pinfunction "VCC_6") (pintype "unspecified"))
    )
    (net (code "39") (name "WAKEUP") (class "Default")
      (node (ref "D2") (pin "1") (pinfunction "K_1") (pintype "unspecified"))
      (node (ref "H5") (pin "2") (pinfunction "2_2") (pintype "unspecified"))
      (node (ref "R6") (pin "1") (pinfunction "1_1") (pintype "input"))
      (node (ref "U2") (pin "3") (pinfunction "EN_3") (pintype "unspecified"))
    )
    (net (code "40") (name "WIORST") (class "Default")
      (node (ref "R14") (pin "1") (pinfunction "1_1") (pintype "input"))
      (node (ref "U8") (pin "26") (pinfunction "PC3(ADC3/PCINT11)_26") (pintype "unspecified"))
    )
    (net (code "41") (name "unconnected-(H3-Pad5)") (class "Default")
      (node (ref "H3") (pin "5") (pinfunction "5_5") (pintype "input"))
    )
    (net (code "42") (name "unconnected-(SW3-Pad1)") (class "Default")
      (node (ref "SW3") (pin "1") (pinfunction "1_1") (pintype "unspecified"))
    )
    (net (code "43") (name "unconnected-(U2-BYP-Pad4)") (class "Default")
      (node (ref "U2") (pin "4") (pinfunction "BYP_4") (pintype "unspecified+no_connect"))
    )
    (net (code "44") (name "unconnected-(U7-PA0-Pad23)") (class "Default")
      (node (ref "U7") (pin "23") (pinfunction "PA0_23") (pintype "unspecified+no_connect"))
    )
    (net (code "45") (name "unconnected-(U7-PA2-Pad19)") (class "Default")
      (node (ref "U7") (pin "19") (pinfunction "PA2_19") (pintype "unspecified+no_connect"))
    )
    (net (code "46") (name "unconnected-(U7-PA3-Pad18)") (class "Default")
      (node (ref "U7") (pin "18") (pinfunction "PA3_18") (pintype "unspecified+no_connect"))
    )
    (net (code "47") (name "unconnected-(U7-PA9-Pad21)") (class "Default")
      (node (ref "U7") (pin "21") (pinfunction "PA9_21") (pintype "unspecified+no_connect"))
    )
    (net (code "48") (name "unconnected-(U7-PA10-Pad27)") (class "Default")
      (node (ref "U7") (pin "27") (pinfunction "PA10_27") (pintype "unspecified+no_connect"))
    )
    (net (code "49") (name "unconnected-(U7-PA13-Pad3)") (class "Default")
      (node (ref "U7") (pin "3") (pinfunction "PA13_3") (pintype "unspecified+no_connect"))
    )
    (net (code "50") (name "unconnected-(U7-PA14-Pad4)") (class "Default")
      (node (ref "U7") (pin "4") (pinfunction "PA14_4") (pintype "unspecified+no_connect"))
    )
    (net (code "51") (name "unconnected-(U7-PA15-Pad6)") (class "Default")
      (node (ref "U7") (pin "6") (pinfunction "PA15_6") (pintype "unspecified+no_connect"))
    )
    (net (code "52") (name "unconnected-(U7-PB0-Pad28)") (class "Default")
      (node (ref "U7") (pin "28") (pinfunction "PB0_28") (pintype "unspecified+no_connect"))
    )
    (net (code "53") (name "unconnected-(U7-PB3-Pad8)") (class "Default")
      (node (ref "U7") (pin "8") (pinfunction "PB3_8") (pintype "unspecified+no_connect"))
    )
    (net (code "54") (name "unconnected-(U7-PB4-Pad7)") (class "Default")
      (node (ref "U7") (pin "7") (pinfunction "PB4_7") (pintype "unspecified+no_connect"))
    )
    (net (code "55") (name "unconnected-(U7-PB5-Pad11)") (class "Default")
      (node (ref "U7") (pin "11") (pinfunction "PB5_11") (pintype "unspecified+no_connect"))
    )
    (net (code "56") (name "unconnected-(U7-PB9-Pad25)") (class "Default")
      (node (ref "U7") (pin "25") (pinfunction "PB9_25") (pintype "unspecified+no_connect"))
    )
    (net (code "57") (name "unconnected-(U7-PB10-Pad20)") (class "Default")
      (node (ref "U7") (pin "20") (pinfunction "PB10_20") (pintype "unspecified+no_connect"))
    )
    (net (code "58") (name "unconnected-(U7-PB14-Pad26)") (class "Default")
      (node (ref "U7") (pin "26") (pinfunction "PB14_26") (pintype "unspecified+no_connect"))
    )
    (net (code "59") (name "unconnected-(U7-PB15-Pad5)") (class "Default")
      (node (ref "U7") (pin "5") (pinfunction "PB15_5") (pintype "unspecified+no_connect"))
    )
    (net (code "60") (name "unconnected-(U7-PC0-Pad13)") (class "Default")
      (node (ref "U7") (pin "13") (pinfunction "PC0_13") (pintype "unspecified+no_connect"))
    )
    (net (code "61") (name "unconnected-(U7-PC1-Pad12)") (class "Default")
      (node (ref "U7") (pin "12") (pinfunction "PC1_12") (pintype "unspecified+no_connect"))
    )
    (net (code "62") (name "unconnected-(U8-(PCINT0{slash}CLKO{slash}ICP1)PB0-Pad12)") (class "Default")
      (node (ref "U8") (pin "12") (pinfunction "(PCINT0/CLKO/ICP1)PB0_12") (pintype "unspecified+no_connect"))
    )
    (net (code "63") (name "unconnected-(U8-(PCINT20{slash}XCK{slash}T0)PD4-Pad2)") (class "Default")
      (node (ref "U8") (pin "2") (pinfunction "(PCINT20/XCK/T0)PD4_2") (pintype "unspecified+no_connect"))
    )
    (net (code "64") (name "unconnected-(U8-(PCINT21{slash}OC0B{slash}T1)PD5-Pad9)") (class "Default")
      (node (ref "U8") (pin "9") (pinfunction "(PCINT21/OC0B/T1)PD5_9") (pintype "unspecified+no_connect"))
    )
    (net (code "65") (name "unconnected-(U8-(PCINT22{slash}OC0A{slash}AIN0)PD6-Pad10)") (class "Default")
      (node (ref "U8") (pin "10") (pinfunction "(PCINT22/OC0A/AIN0)PD6_10") (pintype "unspecified+no_connect"))
    )
    (net (code "66") (name "unconnected-(U8-(PCINT23{slash}AIN1)PD7-Pad11)") (class "Default")
      (node (ref "U8") (pin "11") (pinfunction "(PCINT23/AIN1)PD7_11") (pintype "unspecified+no_connect"))
    )
    (net (code "67") (name "unconnected-(U8-ADC6-Pad19)") (class "Default")
      (node (ref "U8") (pin "19") (pinfunction "ADC6_19") (pintype "unspecified+no_connect"))
    )
    (net (code "68") (name "unconnected-(U8-PC0(ADC0{slash}PCINT8)-Pad23)") (class "Default")
      (node (ref "U8") (pin "23") (pinfunction "PC0(ADC0/PCINT8)_23") (pintype "unspecified+no_connect"))
    )
    (net (code "69") (name "unconnected-(U8-PC1(ADC1{slash}PCINT9)-Pad24)") (class "Default")
      (node (ref "U8") (pin "24") (pinfunction "PC1(ADC1/PCINT9)_24") (pintype "unspecified+no_connect"))
    )
    (net (code "70") (name "unconnected-(U8-PC2(ADC2{slash}PCINT10)-Pad25)") (class "Default")
      (node (ref "U8") (pin "25") (pinfunction "PC2(ADC2/PCINT10)_25") (pintype "unspecified+no_connect"))
    )
    (net (code "71") (name "unconnected-(U8-PD2(INT0{slash}PCINT18)-Pad32)") (class "Default")
      (node (ref "U8") (pin "32") (pinfunction "PD2(INT0/PCINT18)_32") (pintype "unspecified+no_connect"))
    )
  )
)
